# Zynq_programmable_logic.net
KiCad netlist of a schematic drawn in Altium Designer
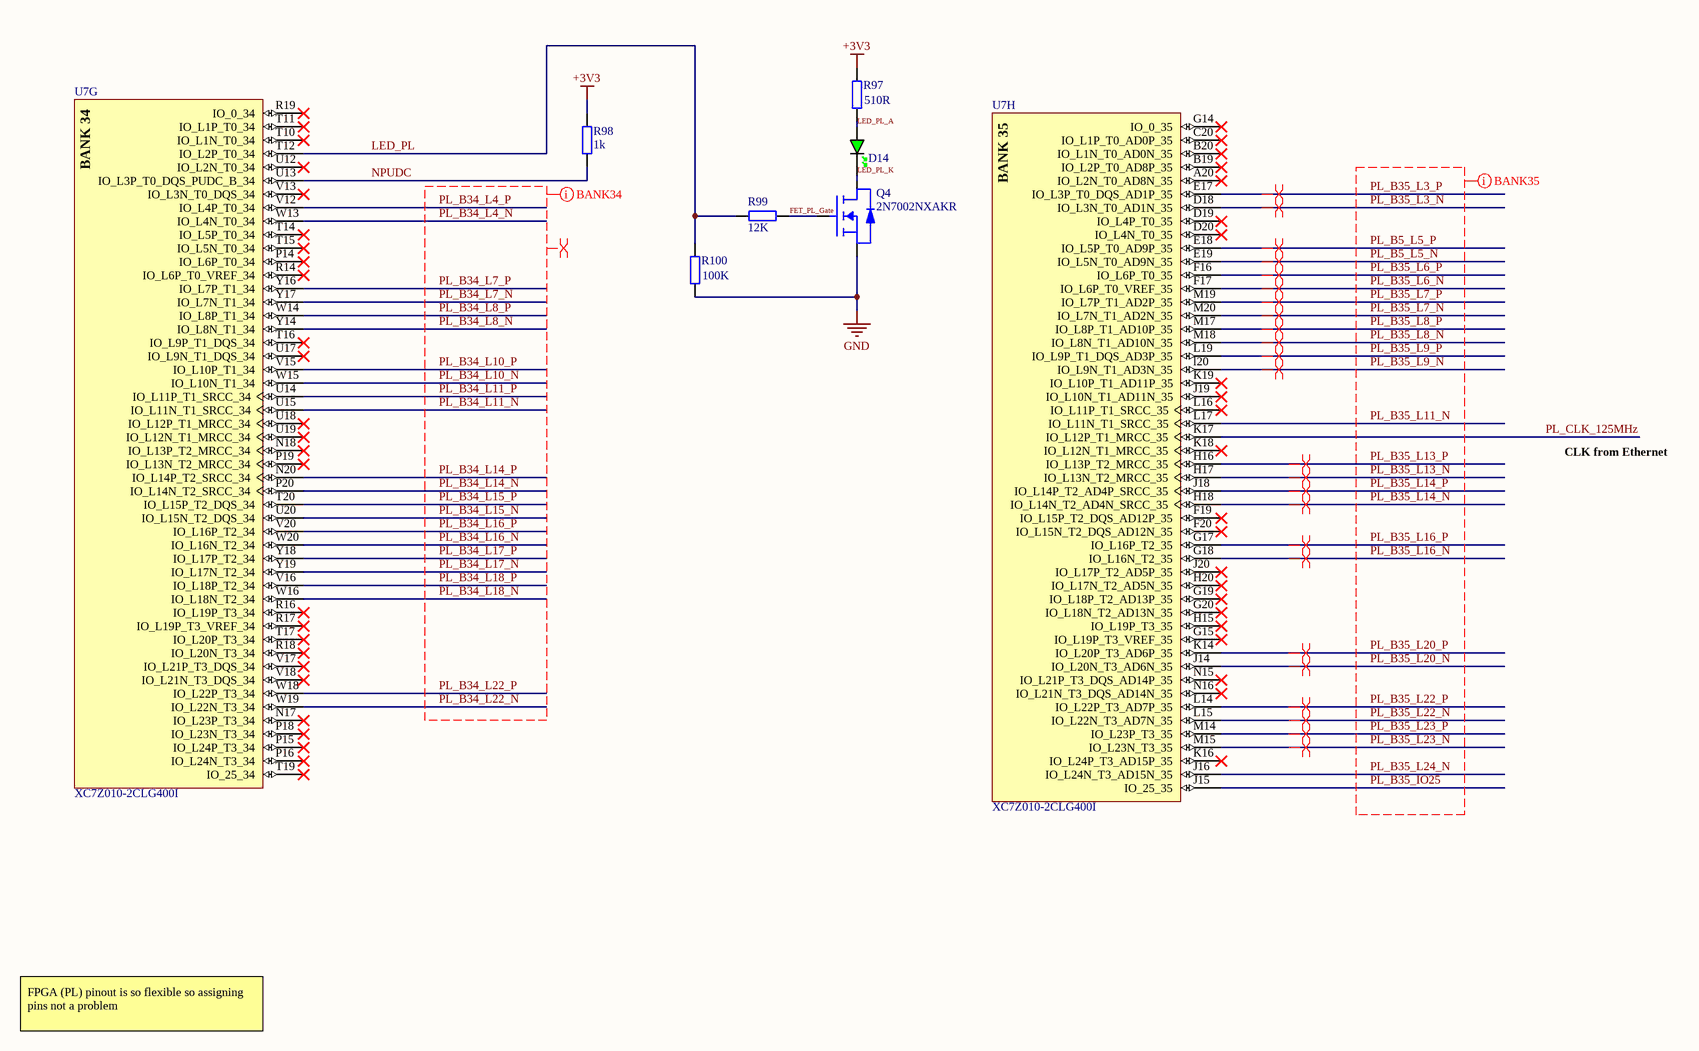
[diagram p0: Zynq programmable logic (PL).SchDoc]

(export (version "E")
  (design (tool "Eeschema 10.0.6"))
  (components
    (comp (ref "D14")
      (value "GREEN")
      (footprint "LED_0402_GREEN")
      (description "LED 0402 GREEN SMD")
      (libsource (lib "Schematic-Lib-PhilsLab") (part "LED_0402_GREEN"))
    )
    (comp (ref "Q4")
      (value "2N7002NXAKR")
      (footprint "SSM3J338R,LF-SOT23-F")
      (description "MOSFET N-Channel Vds=60V Id=300mA with ESD Protection")
      (fields (field (name "MANUFACTURER") "Nexperia"))
      (libsource (lib "Schematic-Lib-PhilsLab") (part "2N7002NXAKR"))
    )
    (comp (ref "R97")
      (value "510R")
      (footprint "RES_0402")
      (description "Resistor SMD 0402")
      (fields (field (name "Comment") "R0402"))
      (libsource (lib "Schematic-Lib-PhilsLab") (part "RES_0402"))
    )
    (comp (ref "R98")
      (value "1k")
      (footprint "RES_0402")
      (description "Resistor SMD 0402")
      (fields (field (name "Comment") "R0402"))
      (libsource (lib "Schematic-Lib-PhilsLab") (part "RES_0402"))
    )
    (comp (ref "R99")
      (value "12K")
      (footprint "RES_0402")
      (description "Resistor SMD 0402")
      (fields (field (name "Comment") "R0402"))
      (libsource (lib "Schematic-Lib-PhilsLab") (part "RES_0402"))
    )
    (comp (ref "R100")
      (value "100K")
      (footprint "RES_0402")
      (description "Resistor SMD 0402")
      (fields (field (name "Comment") "R0402"))
      (libsource (lib "Schematic-Lib-PhilsLab") (part "RES_0402"))
    )
    (comp (ref "U7")
      (value "XC7Z010-2CLG400I")
      (footprint "BGA400C80P20X20_1700X1700X160N")
      (libsource (lib "Zynq_SOM") (part "XC7Z010-2CLG400I"))
    )
  )
  (nets
    (net (code "1") (name "+3V3") (class "Default")
      (node (ref "R97") (pin "1") (pinfunction "1_1") (pintype "passive"))
      (node (ref "R98") (pin "1") (pinfunction "1_1") (pintype "passive"))
    )
    (net (code "2") (name "/FET_PL_Gate") (class "Default")
      (node (ref "Q4") (pin "G") (pinfunction "G_G") (pintype "passive"))
      (node (ref "R99") (pin "1") (pinfunction "1_1") (pintype "passive"))
    )
    (net (code "3") (name "/LED_PL") (class "Default")
      (node (ref "R100") (pin "1") (pinfunction "1_1") (pintype "passive"))
      (node (ref "R99") (pin "2") (pinfunction "2_2") (pintype "passive"))
      (node (ref "U7") (pin "T12") (pinfunction "IO_L2P_T0_34_T12") (pintype "bidirectional"))
    )
    (net (code "4") (name "/LED_PL_A") (class "Default")
      (node (ref "D14") (pin "A") (pinfunction "A_A") (pintype "passive"))
      (node (ref "R97") (pin "2") (pinfunction "2_2") (pintype "passive"))
    )
    (net (code "5") (name "/LED_PL_K") (class "Default")
      (node (ref "D14") (pin "K") (pinfunction "K_K") (pintype "passive"))
      (node (ref "Q4") (pin "D") (pinfunction "D_D") (pintype "passive"))
    )
    (net (code "6") (name "/NPUDC") (class "Default")
      (node (ref "R98") (pin "2") (pinfunction "2_2") (pintype "passive"))
      (node (ref "U7") (pin "U13") (pinfunction "IO_L3P_T0_DQS_PUDC_B_34_U13") (pintype "bidirectional"))
    )
    (net (code "7") (name "/PL_B5_L5_N") (class "Default")
      (node (ref "U7") (pin "E19") (pinfunction "IO_L5N_T0_AD9N_35_E19") (pintype "bidirectional"))
    )
    (net (code "8") (name "/PL_B5_L5_P") (class "Default")
      (node (ref "U7") (pin "E18") (pinfunction "IO_L5P_T0_AD9P_35_E18") (pintype "bidirectional"))
    )
    (net (code "9") (name "/PL_B34_L4_N") (class "Default")
      (node (ref "U7") (pin "W13") (pinfunction "IO_L4N_T0_34_W13") (pintype "bidirectional"))
    )
    (net (code "10") (name "/PL_B34_L4_P") (class "Default")
      (node (ref "U7") (pin "V12") (pinfunction "IO_L4P_T0_34_V12") (pintype "bidirectional"))
    )
    (net (code "11") (name "/PL_B34_L7_N") (class "Default")
      (node (ref "U7") (pin "Y17") (pinfunction "IO_L7N_T1_34_Y17") (pintype "bidirectional"))
    )
    (net (code "12") (name "/PL_B34_L7_P") (class "Default")
      (node (ref "U7") (pin "Y16") (pinfunction "IO_L7P_T1_34_Y16") (pintype "bidirectional"))
    )
    (net (code "13") (name "/PL_B34_L8_N") (class "Default")
      (node (ref "U7") (pin "Y14") (pinfunction "IO_L8N_T1_34_Y14") (pintype "bidirectional"))
    )
    (net (code "14") (name "/PL_B34_L8_P") (class "Default")
      (node (ref "U7") (pin "W14") (pinfunction "IO_L8P_T1_34_W14") (pintype "bidirectional"))
    )
    (net (code "15") (name "/PL_B34_L10_N") (class "Default")
      (node (ref "U7") (pin "W15") (pinfunction "IO_L10N_T1_34_W15") (pintype "bidirectional"))
    )
    (net (code "16") (name "/PL_B34_L10_P") (class "Default")
      (node (ref "U7") (pin "V15") (pinfunction "IO_L10P_T1_34_V15") (pintype "bidirectional"))
    )
    (net (code "17") (name "/PL_B34_L11_N") (class "Default")
      (node (ref "U7") (pin "U15") (pinfunction "IO_L11N_T1_SRCC_34_U15") (pintype "bidirectional"))
    )
    (net (code "18") (name "/PL_B34_L11_P") (class "Default")
      (node (ref "U7") (pin "U14") (pinfunction "IO_L11P_T1_SRCC_34_U14") (pintype "bidirectional"))
    )
    (net (code "19") (name "/PL_B34_L14_N") (class "Default")
      (node (ref "U7") (pin "P20") (pinfunction "IO_L14N_T2_SRCC_34_P20") (pintype "bidirectional"))
    )
    (net (code "20") (name "/PL_B34_L14_P") (class "Default")
      (node (ref "U7") (pin "N20") (pinfunction "IO_L14P_T2_SRCC_34_N20") (pintype "bidirectional"))
    )
    (net (code "21") (name "/PL_B34_L15_N") (class "Default")
      (node (ref "U7") (pin "U20") (pinfunction "IO_L15N_T2_DQS_34_U20") (pintype "bidirectional"))
    )
    (net (code "22") (name "/PL_B34_L15_P") (class "Default")
      (node (ref "U7") (pin "T20") (pinfunction "IO_L15P_T2_DQS_34_T20") (pintype "bidirectional"))
    )
    (net (code "23") (name "/PL_B34_L16_N") (class "Default")
      (node (ref "U7") (pin "W20") (pinfunction "IO_L16N_T2_34_W20") (pintype "bidirectional"))
    )
    (net (code "24") (name "/PL_B34_L16_P") (class "Default")
      (node (ref "U7") (pin "V20") (pinfunction "IO_L16P_T2_34_V20") (pintype "bidirectional"))
    )
    (net (code "25") (name "/PL_B34_L17_N") (class "Default")
      (node (ref "U7") (pin "Y19") (pinfunction "IO_L17N_T2_34_Y19") (pintype "bidirectional"))
    )
    (net (code "26") (name "/PL_B34_L17_P") (class "Default")
      (node (ref "U7") (pin "Y18") (pinfunction "IO_L17P_T2_34_Y18") (pintype "bidirectional"))
    )
    (net (code "27") (name "/PL_B34_L18_N") (class "Default")
      (node (ref "U7") (pin "W16") (pinfunction "IO_L18N_T2_34_W16") (pintype "bidirectional"))
    )
    (net (code "28") (name "/PL_B34_L18_P") (class "Default")
      (node (ref "U7") (pin "V16") (pinfunction "IO_L18P_T2_34_V16") (pintype "bidirectional"))
    )
    (net (code "29") (name "/PL_B34_L22_N") (class "Default")
      (node (ref "U7") (pin "W19") (pinfunction "IO_L22N_T3_34_W19") (pintype "bidirectional"))
    )
    (net (code "30") (name "/PL_B34_L22_P") (class "Default")
      (node (ref "U7") (pin "W18") (pinfunction "IO_L22P_T3_34_W18") (pintype "bidirectional"))
    )
    (net (code "31") (name "/PL_B35_IO25") (class "Default")
      (node (ref "U7") (pin "J15") (pinfunction "IO_25_35_J15") (pintype "bidirectional"))
    )
    (net (code "32") (name "/PL_B35_L3_N") (class "Default")
      (node (ref "U7") (pin "D18") (pinfunction "IO_L3N_T0_AD1N_35_D18") (pintype "bidirectional"))
    )
    (net (code "33") (name "/PL_B35_L3_P") (class "Default")
      (node (ref "U7") (pin "E17") (pinfunction "IO_L3P_T0_DQS_AD1P_35_E17") (pintype "bidirectional"))
    )
    (net (code "34") (name "/PL_B35_L6_N") (class "Default")
      (node (ref "U7") (pin "F17") (pinfunction "IO_L6P_T0_VREF_35_F17") (pintype "bidirectional"))
    )
    (net (code "35") (name "/PL_B35_L6_P") (class "Default")
      (node (ref "U7") (pin "F16") (pinfunction "IO_L6P_T0_35_F16") (pintype "bidirectional"))
    )
    (net (code "36") (name "/PL_B35_L7_N") (class "Default")
      (node (ref "U7") (pin "M20") (pinfunction "IO_L7N_T1_AD2N_35_M20") (pintype "bidirectional"))
    )
    (net (code "37") (name "/PL_B35_L7_P") (class "Default")
      (node (ref "U7") (pin "M19") (pinfunction "IO_L7P_T1_AD2P_35_M19") (pintype "bidirectional"))
    )
    (net (code "38") (name "/PL_B35_L8_N") (class "Default")
      (node (ref "U7") (pin "M18") (pinfunction "IO_L8N_T1_AD10N_35_M18") (pintype "bidirectional"))
    )
    (net (code "39") (name "/PL_B35_L8_P") (class "Default")
      (node (ref "U7") (pin "M17") (pinfunction "IO_L8P_T1_AD10P_35_M17") (pintype "bidirectional"))
    )
    (net (code "40") (name "/PL_B35_L9_N") (class "Default")
      (node (ref "U7") (pin "l20") (pinfunction "IO_L9N_T1_AD3N_35_l20") (pintype "bidirectional"))
    )
    (net (code "41") (name "/PL_B35_L9_P") (class "Default")
      (node (ref "U7") (pin "L19") (pinfunction "IO_L9P_T1_DQS_AD3P_35_L19") (pintype "bidirectional"))
    )
    (net (code "42") (name "/PL_B35_L11_N") (class "Default")
      (node (ref "U7") (pin "L17") (pinfunction "IO_L11N_T1_SRCC_35_L17") (pintype "bidirectional"))
    )
    (net (code "43") (name "/PL_B35_L13_N") (class "Default")
      (node (ref "U7") (pin "H17") (pinfunction "IO_L13N_T2_MRCC_35_H17") (pintype "bidirectional"))
    )
    (net (code "44") (name "/PL_B35_L13_P") (class "Default")
      (node (ref "U7") (pin "H16") (pinfunction "IO_L13P_T2_MRCC_35_H16") (pintype "bidirectional"))
    )
    (net (code "45") (name "/PL_B35_L14_N") (class "Default")
      (node (ref "U7") (pin "H18") (pinfunction "IO_L14N_T2_AD4N_SRCC_35_H18") (pintype "bidirectional"))
    )
    (net (code "46") (name "/PL_B35_L14_P") (class "Default")
      (node (ref "U7") (pin "J18") (pinfunction "IO_L14P_T2_AD4P_SRCC_35_J18") (pintype "bidirectional"))
    )
    (net (code "47") (name "/PL_B35_L16_N") (class "Default")
      (node (ref "U7") (pin "G18") (pinfunction "IO_L16N_T2_35_G18") (pintype "bidirectional"))
    )
    (net (code "48") (name "/PL_B35_L16_P") (class "Default")
      (node (ref "U7") (pin "G17") (pinfunction "IO_L16P_T2_35_G17") (pintype "bidirectional"))
    )
    (net (code "49") (name "/PL_B35_L20_N") (class "Default")
      (node (ref "U7") (pin "J14") (pinfunction "IO_L20N_T3_AD6N_35_J14") (pintype "bidirectional"))
    )
    (net (code "50") (name "/PL_B35_L20_P") (class "Default")
      (node (ref "U7") (pin "K14") (pinfunction "IO_L20P_T3_AD6P_35_K14") (pintype "bidirectional"))
    )
    (net (code "51") (name "/PL_B35_L22_N") (class "Default")
      (node (ref "U7") (pin "L15") (pinfunction "IO_L22N_T3_AD7N_35_L15") (pintype "bidirectional"))
    )
    (net (code "52") (name "/PL_B35_L22_P") (class "Default")
      (node (ref "U7") (pin "L14") (pinfunction "IO_L22P_T3_AD7P_35_L14") (pintype "bidirectional"))
    )
    (net (code "53") (name "/PL_B35_L23_N") (class "Default")
      (node (ref "U7") (pin "M15") (pinfunction "IO_L23N_T3_35_M15") (pintype "bidirectional"))
    )
    (net (code "54") (name "/PL_B35_L23_P") (class "Default")
      (node (ref "U7") (pin "M14") (pinfunction "IO_L23P_T3_35_M14") (pintype "bidirectional"))
    )
    (net (code "55") (name "/PL_B35_L24_N") (class "Default")
      (node (ref "U7") (pin "J16") (pinfunction "IO_L24N_T3_AD15N_35_J16") (pintype "bidirectional"))
    )
    (net (code "56") (name "/PL_CLK_125MHz") (class "Default")
      (node (ref "U7") (pin "K17") (pinfunction "IO_L12P_T1_MRCC_35_K17") (pintype "bidirectional"))
    )
    (net (code "57") (name "GND") (class "Default")
      (node (ref "Q4") (pin "S") (pinfunction "S_S") (pintype "passive"))
      (node (ref "R100") (pin "2") (pinfunction "2_2") (pintype "passive"))
    )
    (net (code "58") (name "unconnected-(U7G-IO_0_34-PadR19)") (class "Default")
      (node (ref "U7") (pin "R19") (pinfunction "IO_0_34_R19") (pintype "bidirectional+no_connect"))
    )
    (net (code "59") (name "unconnected-(U7G-IO_25_34-PadT19)") (class "Default")
      (node (ref "U7") (pin "T19") (pinfunction "IO_25_34_T19") (pintype "bidirectional+no_connect"))
    )
    (net (code "60") (name "unconnected-(U7G-IO_L1N_T0_34-PadT10)") (class "Default")
      (node (ref "U7") (pin "T10") (pinfunction "IO_L1N_T0_34_T10") (pintype "bidirectional+no_connect"))
    )
    (net (code "61") (name "unconnected-(U7G-IO_L1P_T0_34-PadT11)") (class "Default")
      (node (ref "U7") (pin "T11") (pinfunction "IO_L1P_T0_34_T11") (pintype "bidirectional+no_connect"))
    )
    (net (code "62") (name "unconnected-(U7G-IO_L2N_T0_34-PadU12)") (class "Default")
      (node (ref "U7") (pin "U12") (pinfunction "IO_L2N_T0_34_U12") (pintype "bidirectional+no_connect"))
    )
    (net (code "63") (name "unconnected-(U7G-IO_L3N_T0_DQS_34-PadV13)") (class "Default")
      (node (ref "U7") (pin "V13") (pinfunction "IO_L3N_T0_DQS_34_V13") (pintype "bidirectional+no_connect"))
    )
    (net (code "64") (name "unconnected-(U7G-IO_L5N_T0_34-PadT15)") (class "Default")
      (node (ref "U7") (pin "T15") (pinfunction "IO_L5N_T0_34_T15") (pintype "bidirectional+no_connect"))
    )
    (net (code "65") (name "unconnected-(U7G-IO_L5P_T0_34-PadT14)") (class "Default")
      (node (ref "U7") (pin "T14") (pinfunction "IO_L5P_T0_34_T14") (pintype "bidirectional+no_connect"))
    )
    (net (code "66") (name "unconnected-(U7G-IO_L6P_T0_34-PadP14)") (class "Default")
      (node (ref "U7") (pin "P14") (pinfunction "IO_L6P_T0_34_P14") (pintype "bidirectional+no_connect"))
    )
    (net (code "67") (name "unconnected-(U7G-IO_L6P_T0_VREF_34-PadR14)") (class "Default")
      (node (ref "U7") (pin "R14") (pinfunction "IO_L6P_T0_VREF_34_R14") (pintype "bidirectional+no_connect"))
    )
    (net (code "68") (name "unconnected-(U7G-IO_L9N_T1_DQS_34-PadU17)") (class "Default")
      (node (ref "U7") (pin "U17") (pinfunction "IO_L9N_T1_DQS_34_U17") (pintype "bidirectional+no_connect"))
    )
    (net (code "69") (name "unconnected-(U7G-IO_L9P_T1_DQS_34-PadT16)") (class "Default")
      (node (ref "U7") (pin "T16") (pinfunction "IO_L9P_T1_DQS_34_T16") (pintype "bidirectional+no_connect"))
    )
    (net (code "70") (name "unconnected-(U7G-IO_L12N_T1_MRCC_34-PadU19)") (class "Default")
      (node (ref "U7") (pin "U19") (pinfunction "IO_L12N_T1_MRCC_34_U19") (pintype "bidirectional+no_connect"))
    )
    (net (code "71") (name "unconnected-(U7G-IO_L12P_T1_MRCC_34-PadU18)") (class "Default")
      (node (ref "U7") (pin "U18") (pinfunction "IO_L12P_T1_MRCC_34_U18") (pintype "bidirectional+no_connect"))
    )
    (net (code "72") (name "unconnected-(U7G-IO_L13N_T2_MRCC_34-PadP19)") (class "Default")
      (node (ref "U7") (pin "P19") (pinfunction "IO_L13N_T2_MRCC_34_P19") (pintype "bidirectional+no_connect"))
    )
    (net (code "73") (name "unconnected-(U7G-IO_L13P_T2_MRCC_34-PadN18)") (class "Default")
      (node (ref "U7") (pin "N18") (pinfunction "IO_L13P_T2_MRCC_34_N18") (pintype "bidirectional+no_connect"))
    )
    (net (code "74") (name "unconnected-(U7G-IO_L19P_T3_34-PadR16)") (class "Default")
      (node (ref "U7") (pin "R16") (pinfunction "IO_L19P_T3_34_R16") (pintype "bidirectional+no_connect"))
    )
    (net (code "75") (name "unconnected-(U7G-IO_L19P_T3_VREF_34-PadR17)") (class "Default")
      (node (ref "U7") (pin "R17") (pinfunction "IO_L19P_T3_VREF_34_R17") (pintype "bidirectional+no_connect"))
    )
    (net (code "76") (name "unconnected-(U7G-IO_L20N_T3_34-PadR18)") (class "Default")
      (node (ref "U7") (pin "R18") (pinfunction "IO_L20N_T3_34_R18") (pintype "bidirectional+no_connect"))
    )
    (net (code "77") (name "unconnected-(U7G-IO_L20P_T3_34-PadT17)") (class "Default")
      (node (ref "U7") (pin "T17") (pinfunction "IO_L20P_T3_34_T17") (pintype "bidirectional+no_connect"))
    )
    (net (code "78") (name "unconnected-(U7G-IO_L21N_T3_DQS_34-PadV18)") (class "Default")
      (node (ref "U7") (pin "V18") (pinfunction "IO_L21N_T3_DQS_34_V18") (pintype "bidirectional+no_connect"))
    )
    (net (code "79") (name "unconnected-(U7G-IO_L21P_T3_DQS_34-PadV17)") (class "Default")
      (node (ref "U7") (pin "V17") (pinfunction "IO_L21P_T3_DQS_34_V17") (pintype "bidirectional+no_connect"))
    )
    (net (code "80") (name "unconnected-(U7G-IO_L23N_T3_34-PadP18)") (class "Default")
      (node (ref "U7") (pin "P18") (pinfunction "IO_L23N_T3_34_P18") (pintype "bidirectional+no_connect"))
    )
    (net (code "81") (name "unconnected-(U7G-IO_L23P_T3_34-PadN17)") (class "Default")
      (node (ref "U7") (pin "N17") (pinfunction "IO_L23P_T3_34_N17") (pintype "bidirectional+no_connect"))
    )
    (net (code "82") (name "unconnected-(U7G-IO_L24N_T3_34-PadP16)") (class "Default")
      (node (ref "U7") (pin "P16") (pinfunction "IO_L24N_T3_34_P16") (pintype "bidirectional+no_connect"))
    )
    (net (code "83") (name "unconnected-(U7G-IO_L24P_T3_34-PadP15)") (class "Default")
      (node (ref "U7") (pin "P15") (pinfunction "IO_L24P_T3_34_P15") (pintype "bidirectional+no_connect"))
    )
    (net (code "84") (name "unconnected-(U7H-IO_0_35-PadG14)") (class "Default")
      (node (ref "U7") (pin "G14") (pinfunction "IO_0_35_G14") (pintype "bidirectional+no_connect"))
    )
    (net (code "85") (name "unconnected-(U7H-IO_L1N_T0_AD0N_35-PadB20)") (class "Default")
      (node (ref "U7") (pin "B20") (pinfunction "IO_L1N_T0_AD0N_35_B20") (pintype "bidirectional+no_connect"))
    )
    (net (code "86") (name "unconnected-(U7H-IO_L1P_T0_AD0P_35-PadC20)") (class "Default")
      (node (ref "U7") (pin "C20") (pinfunction "IO_L1P_T0_AD0P_35_C20") (pintype "bidirectional+no_connect"))
    )
    (net (code "87") (name "unconnected-(U7H-IO_L2N_T0_AD8N_35-PadA20)") (class "Default")
      (node (ref "U7") (pin "A20") (pinfunction "IO_L2N_T0_AD8N_35_A20") (pintype "bidirectional+no_connect"))
    )
    (net (code "88") (name "unconnected-(U7H-IO_L2P_T0_AD8P_35-PadB19)") (class "Default")
      (node (ref "U7") (pin "B19") (pinfunction "IO_L2P_T0_AD8P_35_B19") (pintype "bidirectional+no_connect"))
    )
    (net (code "89") (name "unconnected-(U7H-IO_L4N_T0_35-PadD20)") (class "Default")
      (node (ref "U7") (pin "D20") (pinfunction "IO_L4N_T0_35_D20") (pintype "bidirectional+no_connect"))
    )
    (net (code "90") (name "unconnected-(U7H-IO_L4P_T0_35-PadD19)") (class "Default")
      (node (ref "U7") (pin "D19") (pinfunction "IO_L4P_T0_35_D19") (pintype "bidirectional+no_connect"))
    )
    (net (code "91") (name "unconnected-(U7H-IO_L10N_T1_AD11N_35-PadJ19)") (class "Default")
      (node (ref "U7") (pin "J19") (pinfunction "IO_L10N_T1_AD11N_35_J19") (pintype "bidirectional+no_connect"))
    )
    (net (code "92") (name "unconnected-(U7H-IO_L10P_T1_AD11P_35-PadK19)") (class "Default")
      (node (ref "U7") (pin "K19") (pinfunction "IO_L10P_T1_AD11P_35_K19") (pintype "bidirectional+no_connect"))
    )
    (net (code "93") (name "unconnected-(U7H-IO_L11P_T1_SRCC_35-PadL16)") (class "Default")
      (node (ref "U7") (pin "L16") (pinfunction "IO_L11P_T1_SRCC_35_L16") (pintype "bidirectional+no_connect"))
    )
    (net (code "94") (name "unconnected-(U7H-IO_L12N_T1_MRCC_35-PadK18)") (class "Default")
      (node (ref "U7") (pin "K18") (pinfunction "IO_L12N_T1_MRCC_35_K18") (pintype "bidirectional+no_connect"))
    )
    (net (code "95") (name "unconnected-(U7H-IO_L15N_T2_DQS_AD12N_35-PadF20)") (class "Default")
      (node (ref "U7") (pin "F20") (pinfunction "IO_L15N_T2_DQS_AD12N_35_F20") (pintype "bidirectional+no_connect"))
    )
    (net (code "96") (name "unconnected-(U7H-IO_L15P_T2_DQS_AD12P_35-PadF19)") (class "Default")
      (node (ref "U7") (pin "F19") (pinfunction "IO_L15P_T2_DQS_AD12P_35_F19") (pintype "bidirectional+no_connect"))
    )
    (net (code "97") (name "unconnected-(U7H-IO_L17N_T2_AD5N_35-PadH20)") (class "Default")
      (node (ref "U7") (pin "H20") (pinfunction "IO_L17N_T2_AD5N_35_H20") (pintype "bidirectional+no_connect"))
    )
    (net (code "98") (name "unconnected-(U7H-IO_L17P_T2_AD5P_35-PadJ20)") (class "Default")
      (node (ref "U7") (pin "J20") (pinfunction "IO_L17P_T2_AD5P_35_J20") (pintype "bidirectional+no_connect"))
    )
    (net (code "99") (name "unconnected-(U7H-IO_L18N_T2_AD13N_35-PadG20)") (class "Default")
      (node (ref "U7") (pin "G20") (pinfunction "IO_L18N_T2_AD13N_35_G20") (pintype "bidirectional+no_connect"))
    )
    (net (code "100") (name "unconnected-(U7H-IO_L18P_T2_AD13P_35-PadG19)") (class "Default")
      (node (ref "U7") (pin "G19") (pinfunction "IO_L18P_T2_AD13P_35_G19") (pintype "bidirectional+no_connect"))
    )
    (net (code "101") (name "unconnected-(U7H-IO_L19P_T3_35-PadH15)") (class "Default")
      (node (ref "U7") (pin "H15") (pinfunction "IO_L19P_T3_35_H15") (pintype "bidirectional+no_connect"))
    )
    (net (code "102") (name "unconnected-(U7H-IO_L19P_T3_VREF_35-PadG15)") (class "Default")
      (node (ref "U7") (pin "G15") (pinfunction "IO_L19P_T3_VREF_35_G15") (pintype "bidirectional+no_connect"))
    )
    (net (code "103") (name "unconnected-(U7H-IO_L21N_T3_DQS_AD14N_35-PadN16)") (class "Default")
      (node (ref "U7") (pin "N16") (pinfunction "IO_L21N_T3_DQS_AD14N_35_N16") (pintype "bidirectional+no_connect"))
    )
    (net (code "104") (name "unconnected-(U7H-IO_L21P_T3_DQS_AD14P_35-PadN15)") (class "Default")
      (node (ref "U7") (pin "N15") (pinfunction "IO_L21P_T3_DQS_AD14P_35_N15") (pintype "bidirectional+no_connect"))
    )
    (net (code "105") (name "unconnected-(U7H-IO_L24P_T3_AD15P_35-PadK16)") (class "Default")
      (node (ref "U7") (pin "K16") (pinfunction "IO_L24P_T3_AD15P_35_K16") (pintype "bidirectional+no_connect"))
    )
  )
)
